# esquema_cubo.net
KiCad netlist of a schematic drawn in EasyEDA
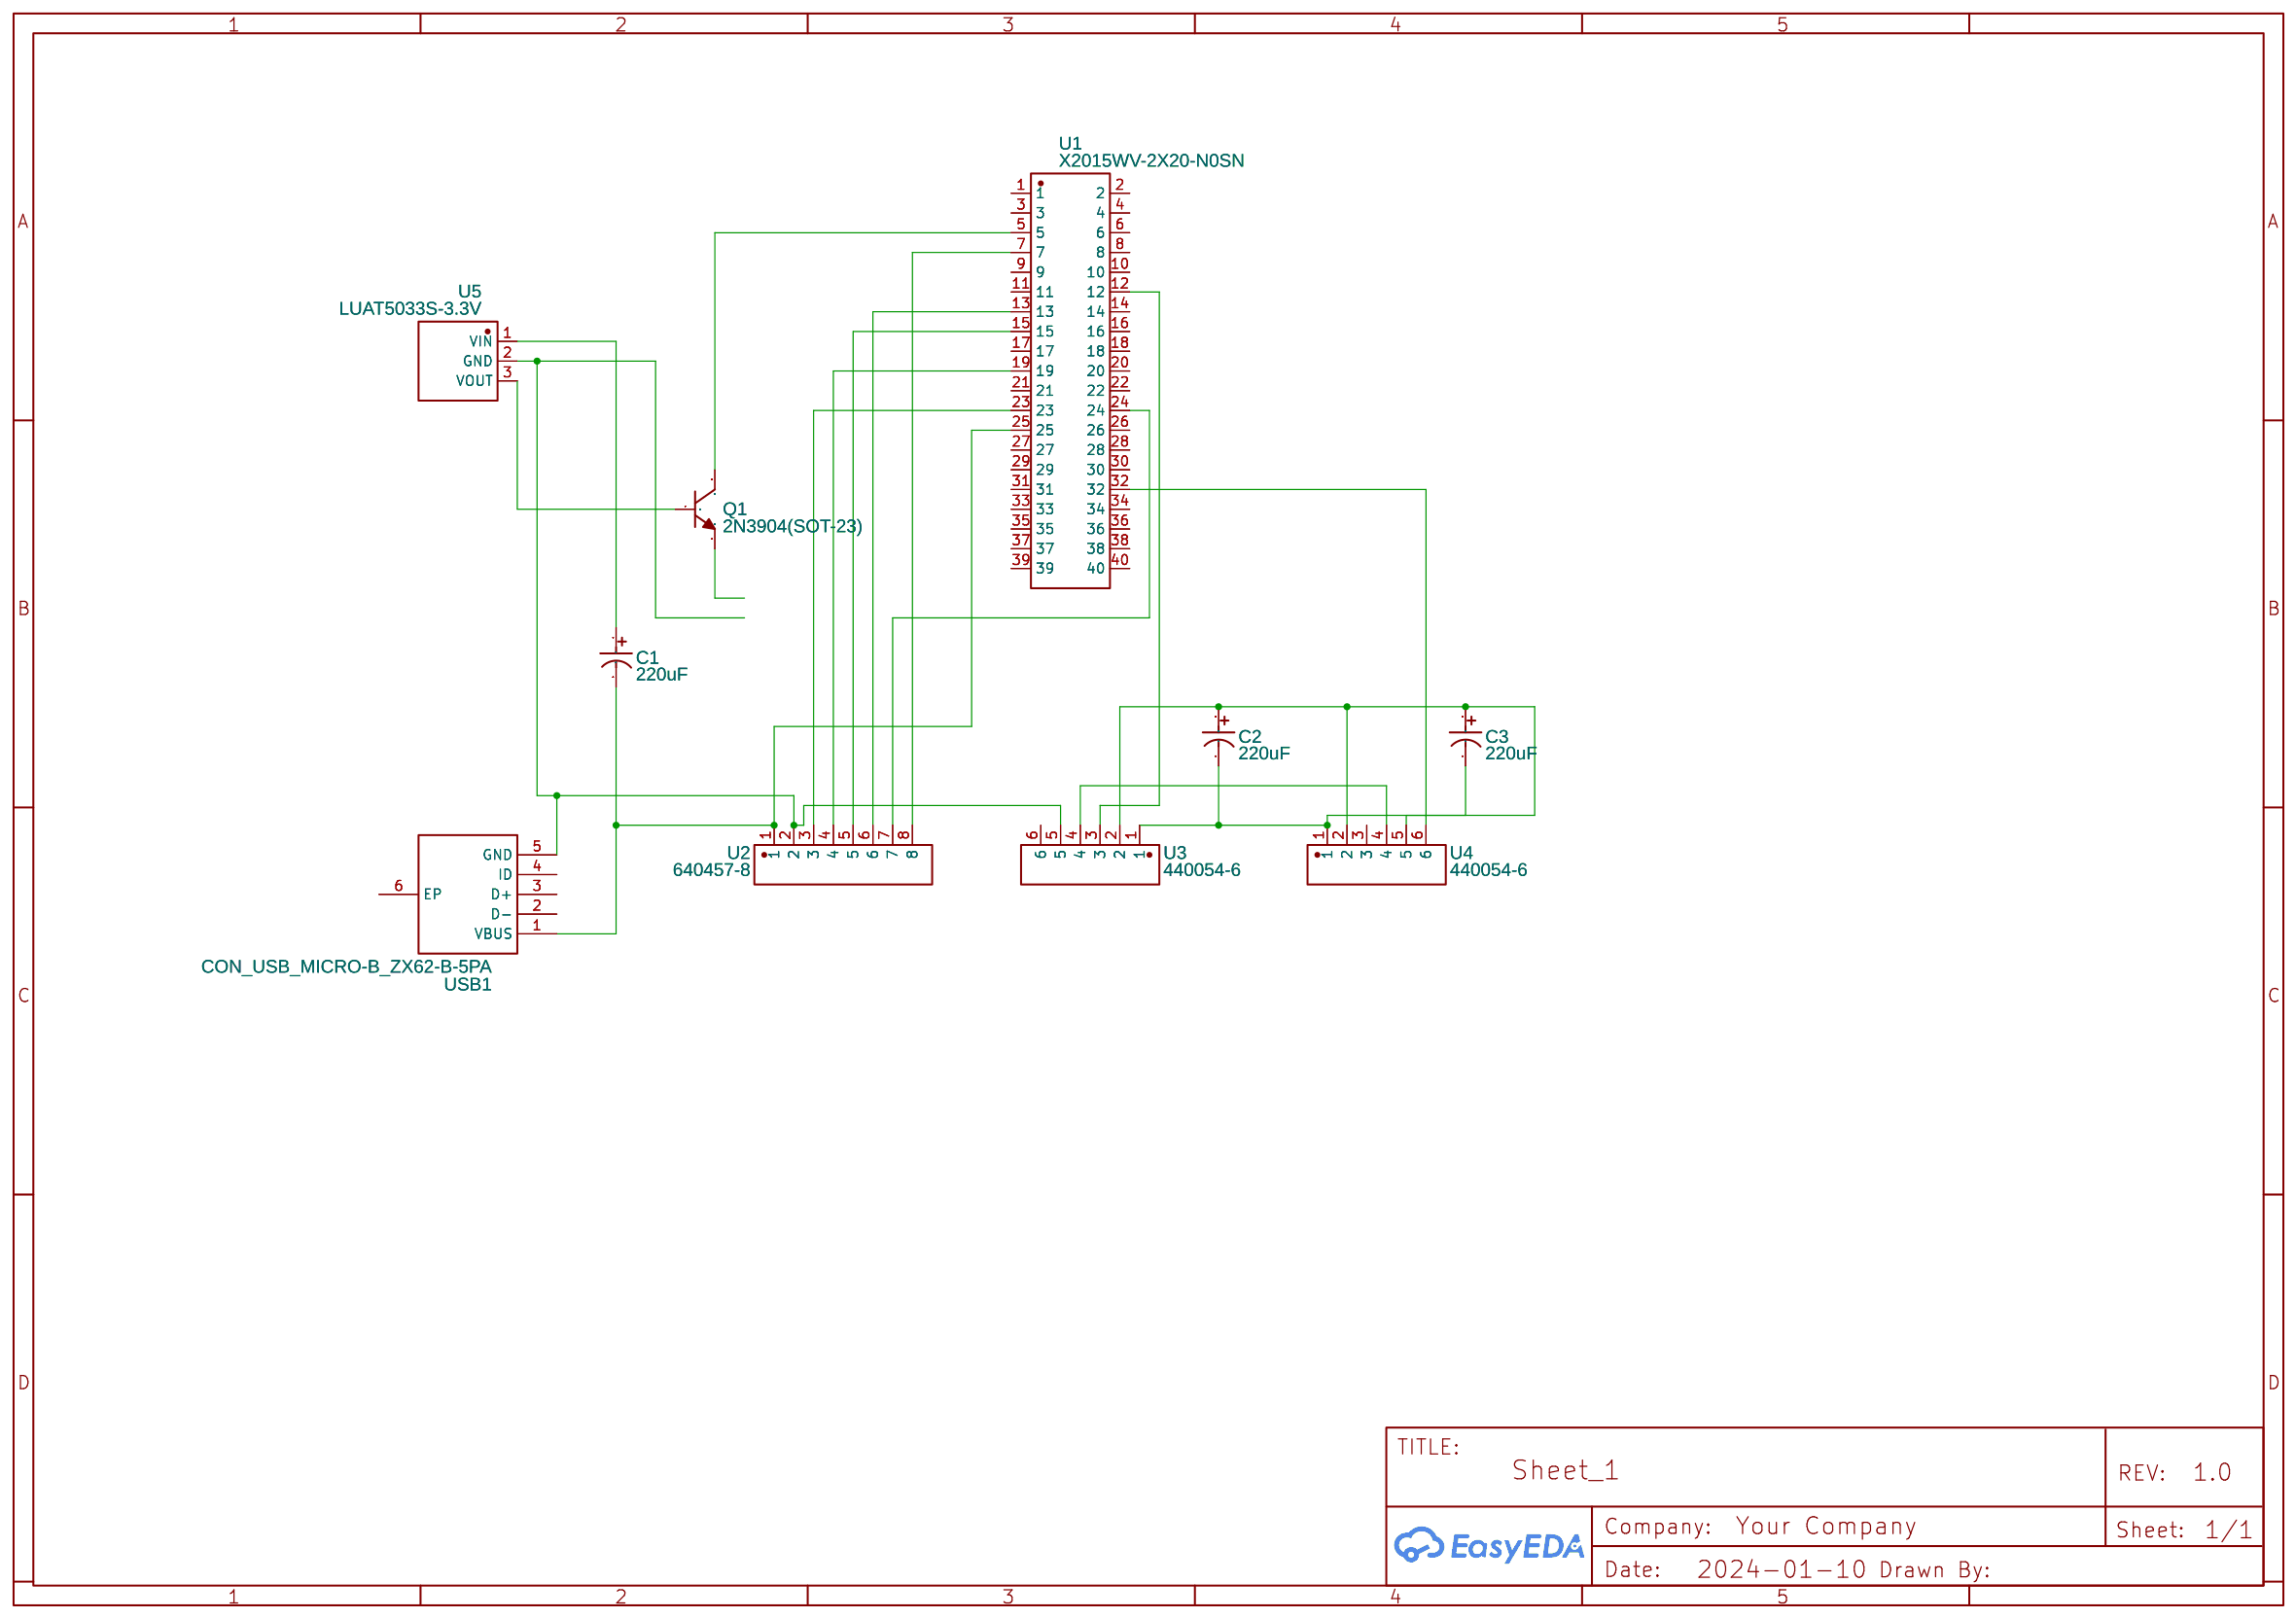
[diagram p0: schematic sheet]

(export (version "E")
  (design (tool "Eeschema 10.0.6"))
  (components
    (comp (ref "C1")
      (value "220uF")
      (fields
        (field (name "Manufacturer Part") "MHA 16V220 6.3*11")
        (field (name "Manufacturer") "SAMYOUNG(韩国三莹)")
      )
      (libsource (lib "") (part "MHA-16V220-6.3*11"))
    )
    (comp (ref "C2")
      (value "220uF")
      (fields
        (field (name "Manufacturer Part") "MHA 16V220 6.3*11")
        (field (name "Manufacturer") "SAMYOUNG(韩国三莹)")
      )
      (libsource (lib "") (part "MHA-16V220-6.3*11"))
    )
    (comp (ref "C3")
      (value "220uF")
      (fields
        (field (name "Manufacturer Part") "MHA 16V220 6.3*11")
        (field (name "Manufacturer") "SAMYOUNG(韩国三莹)")
      )
      (libsource (lib "") (part "MHA-16V220-6.3*11"))
    )
    (comp (ref "Q1")
      (value "2N3904(SOT-23)")
      (fields (field (name "Manufacturer Part") "2n3904S-RTK/PS") (field (name "Manufacturer") "KEC"))
      (libsource (lib "") (part "2N3904(SOT-23)"))
    )
    (comp (ref "U1")
      (value "X2015WV-2X20-N0SN")
      (fields
        (field (name "Manufacturer Part") "X2015WV-2x20-46SN")
        (field (name "Manufacturer") "XKB Connectivity(中国星坤)")
      )
      (libsource (lib "") (part "X2015WV-2X20-N0SN"))
    )
    (comp (ref "U2")
      (value "640457-8")
      (fields (field (name "Manufacturer") "TE Connectivity(美国泰科)"))
      (libsource (lib "") (part "640457-8"))
    )
    (comp (ref "U3")
      (value "440054-6")
      (fields (field (name "Manufacturer") "TE Connectivity(美国泰科)"))
      (libsource (lib "") (part "440054-6_1"))
    )
    (comp (ref "U4")
      (value "440054-6")
      (fields (field (name "Manufacturer") "TE Connectivity(美国泰科)"))
      (libsource (lib "") (part "440054-6"))
    )
    (comp (ref "U5")
      (value "LUAT5033S-3.3V")
      (fields (field (name "Manufacturer Part") "Luat5033S-3.3V"))
      (libsource (lib "") (part "LUAT5033S-3.3V"))
    )
    (comp (ref "USB1")
      (value "CON_USB_MICRO-B_ZX62-B-5PA")
      (libsource (lib "") (part "CON_USB_MICRO-B_ZX62-B-5PA"))
    )
  )
  (nets
    (net (code "1") (name "Net-(C2-Pad1)") (class "Default")
      (node (ref "C2") (pin "1") (pinfunction "1_1") (pintype "input"))
      (node (ref "C3") (pin "1") (pinfunction "1_1") (pintype "input"))
      (node (ref "U3") (pin "2") (pinfunction "2_2") (pintype "unspecified"))
      (node (ref "U4") (pin "2") (pinfunction "2_2") (pintype "unspecified"))
      (node (ref "U4") (pin "5") (pinfunction "5_5") (pintype "unspecified"))
    )
    (net (code "2") (name "Net-(C2-Pad2)") (class "Default")
      (node (ref "C2") (pin "2") (pinfunction "2_2") (pintype "input"))
      (node (ref "C3") (pin "2") (pinfunction "2_2") (pintype "input"))
      (node (ref "U3") (pin "1") (pinfunction "1_1") (pintype "unspecified"))
      (node (ref "U4") (pin "1") (pinfunction "1_1") (pintype "unspecified"))
    )
    (net (code "3") (name "Net-(Q1-B)") (class "Default")
      (node (ref "Q1") (pin "2") (pinfunction "B_2") (pintype "input"))
      (node (ref "U5") (pin "3") (pinfunction "VOUT_3") (pintype "unspecified"))
    )
    (net (code "4") (name "Net-(Q1-C)") (class "Default")
      (node (ref "Q1") (pin "3") (pinfunction "C_3") (pintype "input"))
      (node (ref "U1") (pin "5") (pinfunction "5_5") (pintype "unspecified"))
    )
    (net (code "5") (name "Net-(U1-Pad7)") (class "Default")
      (node (ref "U1") (pin "7") (pinfunction "7_7") (pintype "unspecified"))
      (node (ref "U2") (pin "8") (pinfunction "8_8") (pintype "unspecified"))
    )
    (net (code "6") (name "Net-(U1-Pad12)") (class "Default")
      (node (ref "U1") (pin "12") (pinfunction "12_12") (pintype "unspecified"))
      (node (ref "U3") (pin "3") (pinfunction "3_3") (pintype "unspecified"))
    )
    (net (code "7") (name "Net-(U1-Pad13)") (class "Default")
      (node (ref "U1") (pin "13") (pinfunction "13_13") (pintype "unspecified"))
      (node (ref "U2") (pin "6") (pinfunction "6_6") (pintype "unspecified"))
    )
    (net (code "8") (name "Net-(U1-Pad15)") (class "Default")
      (node (ref "U1") (pin "15") (pinfunction "15_15") (pintype "unspecified"))
      (node (ref "U2") (pin "5") (pinfunction "5_5") (pintype "unspecified"))
    )
    (net (code "9") (name "Net-(U1-Pad19)") (class "Default")
      (node (ref "U1") (pin "19") (pinfunction "19_19") (pintype "unspecified"))
      (node (ref "U2") (pin "4") (pinfunction "4_4") (pintype "unspecified"))
    )
    (net (code "10") (name "Net-(U1-Pad23)") (class "Default")
      (node (ref "U1") (pin "23") (pinfunction "23_23") (pintype "unspecified"))
      (node (ref "U2") (pin "3") (pinfunction "3_3") (pintype "unspecified"))
    )
    (net (code "11") (name "Net-(U1-Pad24)") (class "Default")
      (node (ref "U1") (pin "24") (pinfunction "24_24") (pintype "unspecified"))
      (node (ref "U2") (pin "7") (pinfunction "7_7") (pintype "unspecified"))
    )
    (net (code "12") (name "Net-(U1-Pad32)") (class "Default")
      (node (ref "U1") (pin "32") (pinfunction "32_32") (pintype "unspecified"))
      (node (ref "U4") (pin "6") (pinfunction "6_6") (pintype "unspecified"))
    )
    (net (code "13") (name "Net-(U3-Pad4)") (class "Default")
      (node (ref "U3") (pin "4") (pinfunction "4_4") (pintype "unspecified"))
      (node (ref "U4") (pin "4") (pinfunction "4_4") (pintype "unspecified"))
    )
    (net (code "14") (name "Net-(U5-GND)") (class "Default")
      (node (ref "U2") (pin "2") (pinfunction "2_2") (pintype "unspecified"))
      (node (ref "U3") (pin "5") (pinfunction "5_5") (pintype "unspecified"))
      (node (ref "U5") (pin "2") (pinfunction "GND_2") (pintype "unspecified"))
      (node (ref "USB1") (pin "5") (pinfunction "GND_5") (pintype "unspecified"))
    )
    (net (code "15") (name "Net-(U5-VIN)") (class "Default")
      (node (ref "C1") (pin "1") (pinfunction "1_1") (pintype "input"))
      (node (ref "U5") (pin "1") (pinfunction "VIN_1") (pintype "unspecified"))
    )
    (net (code "16") (name "Net-(USB1-VBUS)") (class "Default")
      (node (ref "C1") (pin "2") (pinfunction "2_2") (pintype "input"))
      (node (ref "U1") (pin "25") (pinfunction "25_25") (pintype "unspecified"))
      (node (ref "U2") (pin "1") (pinfunction "1_1") (pintype "unspecified"))
      (node (ref "USB1") (pin "1") (pinfunction "VBUS_1") (pintype "unspecified"))
    )
    (net (code "17") (name "unconnected-(Q1-E-Pad1)") (class "Default")
      (node (ref "Q1") (pin "1") (pinfunction "E_1") (pintype "input"))
    )
    (net (code "18") (name "unconnected-(U1-Pad1)") (class "Default")
      (node (ref "U1") (pin "1") (pinfunction "1_1") (pintype "unspecified"))
    )
    (net (code "19") (name "unconnected-(U1-Pad2)") (class "Default")
      (node (ref "U1") (pin "2") (pinfunction "2_2") (pintype "unspecified"))
    )
    (net (code "20") (name "unconnected-(U1-Pad3)") (class "Default")
      (node (ref "U1") (pin "3") (pinfunction "3_3") (pintype "unspecified"))
    )
    (net (code "21") (name "unconnected-(U1-Pad4)") (class "Default")
      (node (ref "U1") (pin "4") (pinfunction "4_4") (pintype "unspecified"))
    )
    (net (code "22") (name "unconnected-(U1-Pad6)") (class "Default")
      (node (ref "U1") (pin "6") (pinfunction "6_6") (pintype "unspecified"))
    )
    (net (code "23") (name "unconnected-(U1-Pad8)") (class "Default")
      (node (ref "U1") (pin "8") (pinfunction "8_8") (pintype "unspecified"))
    )
    (net (code "24") (name "unconnected-(U1-Pad9)") (class "Default")
      (node (ref "U1") (pin "9") (pinfunction "9_9") (pintype "unspecified"))
    )
    (net (code "25") (name "unconnected-(U1-Pad10)") (class "Default")
      (node (ref "U1") (pin "10") (pinfunction "10_10") (pintype "unspecified"))
    )
    (net (code "26") (name "unconnected-(U1-Pad11)") (class "Default")
      (node (ref "U1") (pin "11") (pinfunction "11_11") (pintype "unspecified"))
    )
    (net (code "27") (name "unconnected-(U1-Pad14)") (class "Default")
      (node (ref "U1") (pin "14") (pinfunction "14_14") (pintype "unspecified"))
    )
    (net (code "28") (name "unconnected-(U1-Pad16)") (class "Default")
      (node (ref "U1") (pin "16") (pinfunction "16_16") (pintype "unspecified"))
    )
    (net (code "29") (name "unconnected-(U1-Pad17)") (class "Default")
      (node (ref "U1") (pin "17") (pinfunction "17_17") (pintype "unspecified"))
    )
    (net (code "30") (name "unconnected-(U1-Pad18)") (class "Default")
      (node (ref "U1") (pin "18") (pinfunction "18_18") (pintype "unspecified"))
    )
    (net (code "31") (name "unconnected-(U1-Pad20)") (class "Default")
      (node (ref "U1") (pin "20") (pinfunction "20_20") (pintype "unspecified"))
    )
    (net (code "32") (name "unconnected-(U1-Pad21)") (class "Default")
      (node (ref "U1") (pin "21") (pinfunction "21_21") (pintype "unspecified"))
    )
    (net (code "33") (name "unconnected-(U1-Pad22)") (class "Default")
      (node (ref "U1") (pin "22") (pinfunction "22_22") (pintype "unspecified"))
    )
    (net (code "34") (name "unconnected-(U1-Pad26)") (class "Default")
      (node (ref "U1") (pin "26") (pinfunction "26_26") (pintype "unspecified"))
    )
    (net (code "35") (name "unconnected-(U1-Pad27)") (class "Default")
      (node (ref "U1") (pin "27") (pinfunction "27_27") (pintype "unspecified"))
    )
    (net (code "36") (name "unconnected-(U1-Pad28)") (class "Default")
      (node (ref "U1") (pin "28") (pinfunction "28_28") (pintype "unspecified"))
    )
    (net (code "37") (name "unconnected-(U1-Pad29)") (class "Default")
      (node (ref "U1") (pin "29") (pinfunction "29_29") (pintype "unspecified"))
    )
    (net (code "38") (name "unconnected-(U1-Pad30)") (class "Default")
      (node (ref "U1") (pin "30") (pinfunction "30_30") (pintype "unspecified"))
    )
    (net (code "39") (name "unconnected-(U1-Pad31)") (class "Default")
      (node (ref "U1") (pin "31") (pinfunction "31_31") (pintype "unspecified"))
    )
    (net (code "40") (name "unconnected-(U1-Pad33)") (class "Default")
      (node (ref "U1") (pin "33") (pinfunction "33_33") (pintype "unspecified"))
    )
    (net (code "41") (name "unconnected-(U1-Pad34)") (class "Default")
      (node (ref "U1") (pin "34") (pinfunction "34_34") (pintype "unspecified"))
    )
    (net (code "42") (name "unconnected-(U1-Pad35)") (class "Default")
      (node (ref "U1") (pin "35") (pinfunction "35_35") (pintype "unspecified"))
    )
    (net (code "43") (name "unconnected-(U1-Pad36)") (class "Default")
      (node (ref "U1") (pin "36") (pinfunction "36_36") (pintype "unspecified"))
    )
    (net (code "44") (name "unconnected-(U1-Pad37)") (class "Default")
      (node (ref "U1") (pin "37") (pinfunction "37_37") (pintype "unspecified"))
    )
    (net (code "45") (name "unconnected-(U1-Pad38)") (class "Default")
      (node (ref "U1") (pin "38") (pinfunction "38_38") (pintype "unspecified"))
    )
    (net (code "46") (name "unconnected-(U1-Pad39)") (class "Default")
      (node (ref "U1") (pin "39") (pinfunction "39_39") (pintype "unspecified"))
    )
    (net (code "47") (name "unconnected-(U1-Pad40)") (class "Default")
      (node (ref "U1") (pin "40") (pinfunction "40_40") (pintype "unspecified"))
    )
    (net (code "48") (name "unconnected-(U3-Pad6)") (class "Default")
      (node (ref "U3") (pin "6") (pinfunction "6_6") (pintype "unspecified"))
    )
    (net (code "49") (name "unconnected-(U4-Pad3)") (class "Default")
      (node (ref "U4") (pin "3") (pinfunction "3_3") (pintype "unspecified"))
    )
    (net (code "50") (name "unconnected-(USB1-D+-Pad3)") (class "Default")
      (node (ref "USB1") (pin "3") (pinfunction "D+_3") (pintype "unspecified"))
    )
    (net (code "51") (name "unconnected-(USB1-D--Pad2)") (class "Default")
      (node (ref "USB1") (pin "2") (pinfunction "D-_2") (pintype "unspecified"))
    )
    (net (code "52") (name "unconnected-(USB1-EP-Pad6)") (class "Default")
      (node (ref "USB1") (pin "6") (pinfunction "EP_6") (pintype "unspecified"))
    )
    (net (code "53") (name "unconnected-(USB1-ID-Pad4)") (class "Default")
      (node (ref "USB1") (pin "4") (pinfunction "ID_4") (pintype "unspecified"))
    )
  )
)
